# humidity_sensor.net
KiCad netlist of a schematic drawn in Altium Designer
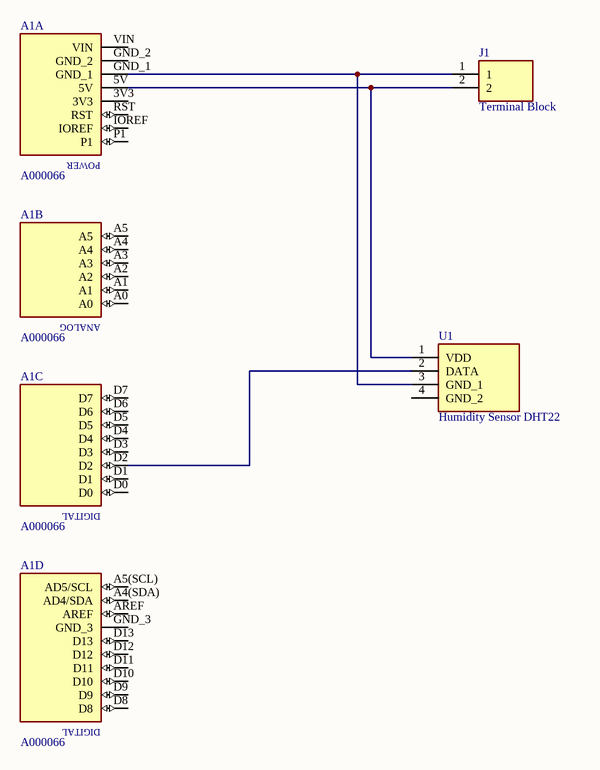
[diagram p0: humidity sensor.SchDoc]

(export (version "E")
  (design (tool "Eeschema 10.0.6"))
  (components
    (comp (ref "A1")
      (value "A000066")
      (footprint "A000066:ARDUINO_A000066")
      (fields (field (name "MF") "{'manufacturer': u'Arduino'}") (field (name "MP") "ARDUINO UNO REV3"))
      (libsource (lib "A000066") (part "A000066"))
    )
    (comp (ref "J1")
      (value "Terminal Block")
      (footprint "humidity sensor:TB00250002BE")
      (description "Connector")
      (fields
        (field (name "MANUFACTURER_PART_NUMBER") "TB002-500-02BE")
        (field (name "MOUSER PART NUMBER") "490-TB002-500-02BE")
      )
      (libsource (lib "humidity sensor") (part "TB002-500-02BE"))
    )
    (comp (ref "U1")
      (value "Humidity Sensor DHT22")
      (footprint "humidity sensor:314010001")
      (fields
        (field (name "MANUFACTURER_PART_NUMBER") "314010001")
        (field (name "MOUSER PART NUMBER") "713-314010001")
      )
      (libsource (lib "humidity sensor") (part "314010001"))
    )
  )
  (nets
    (net (code "1") (name "Net-(U1-DATA)") (class "Default")
      (node (ref "A1") (pin "D2") (pinfunction "D2_D2") (pintype "bidirectional"))
      (node (ref "U1") (pin "2") (pinfunction "DATA_2") (pintype "passive"))
    )
    (net (code "2") (name "Net-(U1-GND_1)") (class "Default")
      (node (ref "A1") (pin "GND_1") (pinfunction "GND_1_GND_1") (pintype "power_in"))
      (node (ref "J1") (pin "1") (pinfunction "1_1") (pintype "passive"))
      (node (ref "U1") (pin "3") (pinfunction "GND_1_3") (pintype "passive"))
    )
    (net (code "3") (name "Net-(U1-VDD)") (class "Default")
      (node (ref "A1") (pin "5V") (pinfunction "5V_5V") (pintype "power_in"))
      (node (ref "J1") (pin "2") (pinfunction "2_2") (pintype "passive"))
      (node (ref "U1") (pin "1") (pinfunction "VDD_1") (pintype "passive"))
    )
    (net (code "4") (name "unconnected-(A1-Pad3V3)") (class "Default")
      (node (ref "A1") (pin "3V3") (pinfunction "3V3_3V3") (pintype "power_in"))
    )
    (net (code "5") (name "unconnected-(A1-PadA0)") (class "Default")
      (node (ref "A1") (pin "A0") (pinfunction "A0_A0") (pintype "bidirectional"))
    )
    (net (code "6") (name "unconnected-(A1-PadA1)") (class "Default")
      (node (ref "A1") (pin "A1") (pinfunction "A1_A1") (pintype "bidirectional"))
    )
    (net (code "7") (name "unconnected-(A1-PadA2)") (class "Default")
      (node (ref "A1") (pin "A2") (pinfunction "A2_A2") (pintype "bidirectional"))
    )
    (net (code "8") (name "unconnected-(A1-PadA3)") (class "Default")
      (node (ref "A1") (pin "A3") (pinfunction "A3_A3") (pintype "bidirectional"))
    )
    (net (code "9") (name "unconnected-(A1-PadA4)") (class "Default")
      (node (ref "A1") (pin "A4") (pinfunction "A4_A4") (pintype "bidirectional"))
    )
    (net (code "10") (name "unconnected-(A1-PadA5)") (class "Default")
      (node (ref "A1") (pin "A5") (pinfunction "A5_A5") (pintype "bidirectional"))
    )
    (net (code "11") (name "unconnected-(A1-PadAREF)") (class "Default")
      (node (ref "A1") (pin "AREF") (pinfunction "AREF_AREF") (pintype "bidirectional"))
    )
    (net (code "12") (name "unconnected-(A1-PadD0)") (class "Default")
      (node (ref "A1") (pin "D0") (pinfunction "D0_D0") (pintype "bidirectional"))
    )
    (net (code "13") (name "unconnected-(A1-PadD1)") (class "Default")
      (node (ref "A1") (pin "D1") (pinfunction "D1_D1") (pintype "bidirectional"))
    )
    (net (code "14") (name "unconnected-(A1-PadD3)") (class "Default")
      (node (ref "A1") (pin "D3") (pinfunction "D3_D3") (pintype "bidirectional"))
    )
    (net (code "15") (name "unconnected-(A1-PadD4)") (class "Default")
      (node (ref "A1") (pin "D4") (pinfunction "D4_D4") (pintype "bidirectional"))
    )
    (net (code "16") (name "unconnected-(A1-PadD5)") (class "Default")
      (node (ref "A1") (pin "D5") (pinfunction "D5_D5") (pintype "bidirectional"))
    )
    (net (code "17") (name "unconnected-(A1-PadD6)") (class "Default")
      (node (ref "A1") (pin "D6") (pinfunction "D6_D6") (pintype "bidirectional"))
    )
    (net (code "18") (name "unconnected-(A1-PadD7)") (class "Default")
      (node (ref "A1") (pin "D7") (pinfunction "D7_D7") (pintype "bidirectional"))
    )
    (net (code "19") (name "unconnected-(A1-PadD8)") (class "Default")
      (node (ref "A1") (pin "D8") (pinfunction "D8_D8") (pintype "bidirectional"))
    )
    (net (code "20") (name "unconnected-(A1-PadD9)") (class "Default")
      (node (ref "A1") (pin "D9") (pinfunction "D9_D9") (pintype "bidirectional"))
    )
    (net (code "21") (name "unconnected-(A1-PadD10)") (class "Default")
      (node (ref "A1") (pin "D10") (pinfunction "D10_D10") (pintype "bidirectional"))
    )
    (net (code "22") (name "unconnected-(A1-PadD11)") (class "Default")
      (node (ref "A1") (pin "D11") (pinfunction "D11_D11") (pintype "bidirectional"))
    )
    (net (code "23") (name "unconnected-(A1-PadD12)") (class "Default")
      (node (ref "A1") (pin "D12") (pinfunction "D12_D12") (pintype "bidirectional"))
    )
    (net (code "24") (name "unconnected-(A1-PadD13)") (class "Default")
      (node (ref "A1") (pin "D13") (pinfunction "D13_D13") (pintype "bidirectional"))
    )
    (net (code "25") (name "unconnected-(A1-PadGND_2)") (class "Default")
      (node (ref "A1") (pin "GND_2") (pinfunction "GND_2_GND_2") (pintype "power_in"))
    )
    (net (code "26") (name "unconnected-(A1-PadGND_3)") (class "Default")
      (node (ref "A1") (pin "GND_3") (pinfunction "GND_3_GND_3") (pintype "power_in"))
    )
    (net (code "27") (name "unconnected-(A1-PadIOREF)") (class "Default")
      (node (ref "A1") (pin "IOREF") (pinfunction "IOREF_IOREF") (pintype "bidirectional"))
    )
    (net (code "28") (name "unconnected-(A1-PadP1)") (class "Default")
      (node (ref "A1") (pin "P1") (pinfunction "P1_P1") (pintype "bidirectional"))
    )
    (net (code "29") (name "unconnected-(A1-PadRST)") (class "Default")
      (node (ref "A1") (pin "RST") (pinfunction "RST_RST") (pintype "bidirectional"))
    )
    (net (code "30") (name "unconnected-(A1-PadVIN)") (class "Default")
      (node (ref "A1") (pin "VIN") (pinfunction "VIN_VIN") (pintype "power_in"))
    )
    (net (code "31") (name "unconnected-(A1D-AD4{slash}SDA-PadA4(SDA))") (class "Default")
      (node (ref "A1") (pin "A4(SDA)") (pinfunction "AD4/SDA_A4(SDA)") (pintype "bidirectional"))
    )
    (net (code "32") (name "unconnected-(A1D-AD5{slash}SCL-PadA5(SCL))") (class "Default")
      (node (ref "A1") (pin "A5(SCL)") (pinfunction "AD5/SCL_A5(SCL)") (pintype "bidirectional"))
    )
    (net (code "33") (name "unconnected-(U1-GND_2-Pad4)") (class "Default")
      (node (ref "U1") (pin "4") (pinfunction "GND_2_4") (pintype "passive"))
    )
  )
)
